# Full_Power_Board.net
KiCad netlist of a schematic drawn in Altium Designer
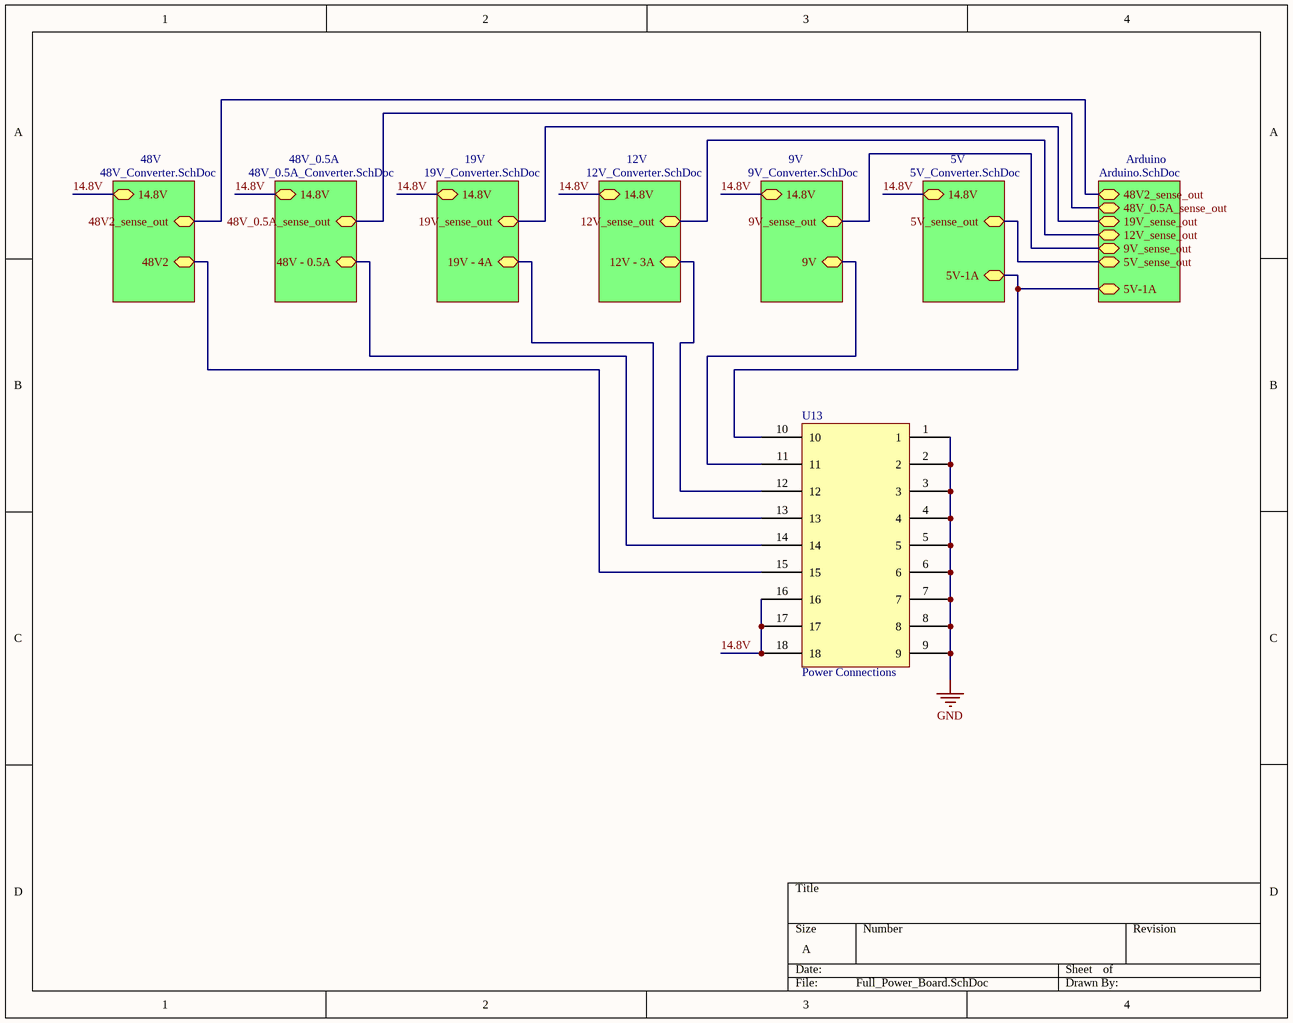
[diagram p0: Full_Power_Board.SchDoc]

(export (version "E")
  (design (tool "Eeschema 10.0.6"))
  (components
    (comp (ref "U13")
      (value "Power Connections")
      (footprint "Molex Connector")
      (libsource (lib "Power_Board_Parts_Library") (part "Molex Connector"))
    )
  )
  (nets
    (net (code "1") (name "/5V-1A") (class "Default")
      (node (ref "U13") (pin "10") (pinfunction "10_10") (pintype "passive"))
    )
    (net (code "3") (name "/9V") (class "Default")
      (node (ref "U13") (pin "11") (pinfunction "11_11") (pintype "passive"))
    )
    (net (code "5") (name "/12V - 3A") (class "Default")
      (node (ref "U13") (pin "12") (pinfunction "12_12") (pintype "passive"))
    )
    (net (code "7") (name "/14.8V") (class "Default")
      (node (ref "U13") (pin "16") (pinfunction "16_16") (pintype "passive"))
      (node (ref "U13") (pin "17") (pinfunction "17_17") (pintype "passive"))
      (node (ref "U13") (pin "18") (pinfunction "18_18") (pintype "passive"))
    )
    (net (code "8") (name "/19V - 4A") (class "Default")
      (node (ref "U13") (pin "13") (pinfunction "13_13") (pintype "passive"))
    )
    (net (code "10") (name "/48V - 0.5A") (class "Default")
      (node (ref "U13") (pin "14") (pinfunction "14_14") (pintype "passive"))
    )
    (net (code "11") (name "/48V2") (class "Default")
      (node (ref "U13") (pin "15") (pinfunction "15_15") (pintype "passive"))
    )
    (net (code "14") (name "GND") (class "Default")
      (node (ref "U13") (pin "1") (pinfunction "1_1") (pintype "passive"))
      (node (ref "U13") (pin "2") (pinfunction "2_2") (pintype "passive"))
      (node (ref "U13") (pin "3") (pinfunction "3_3") (pintype "passive"))
      (node (ref "U13") (pin "4") (pinfunction "4_4") (pintype "passive"))
      (node (ref "U13") (pin "5") (pinfunction "5_5") (pintype "passive"))
      (node (ref "U13") (pin "6") (pinfunction "6_6") (pintype "passive"))
      (node (ref "U13") (pin "7") (pinfunction "7_7") (pintype "passive"))
      (node (ref "U13") (pin "8") (pinfunction "8_8") (pintype "passive"))
      (node (ref "U13") (pin "9") (pinfunction "9_9") (pintype "passive"))
    )
  )
)
